# MCU.net
KiCad netlist of a schematic drawn in Altium Designer
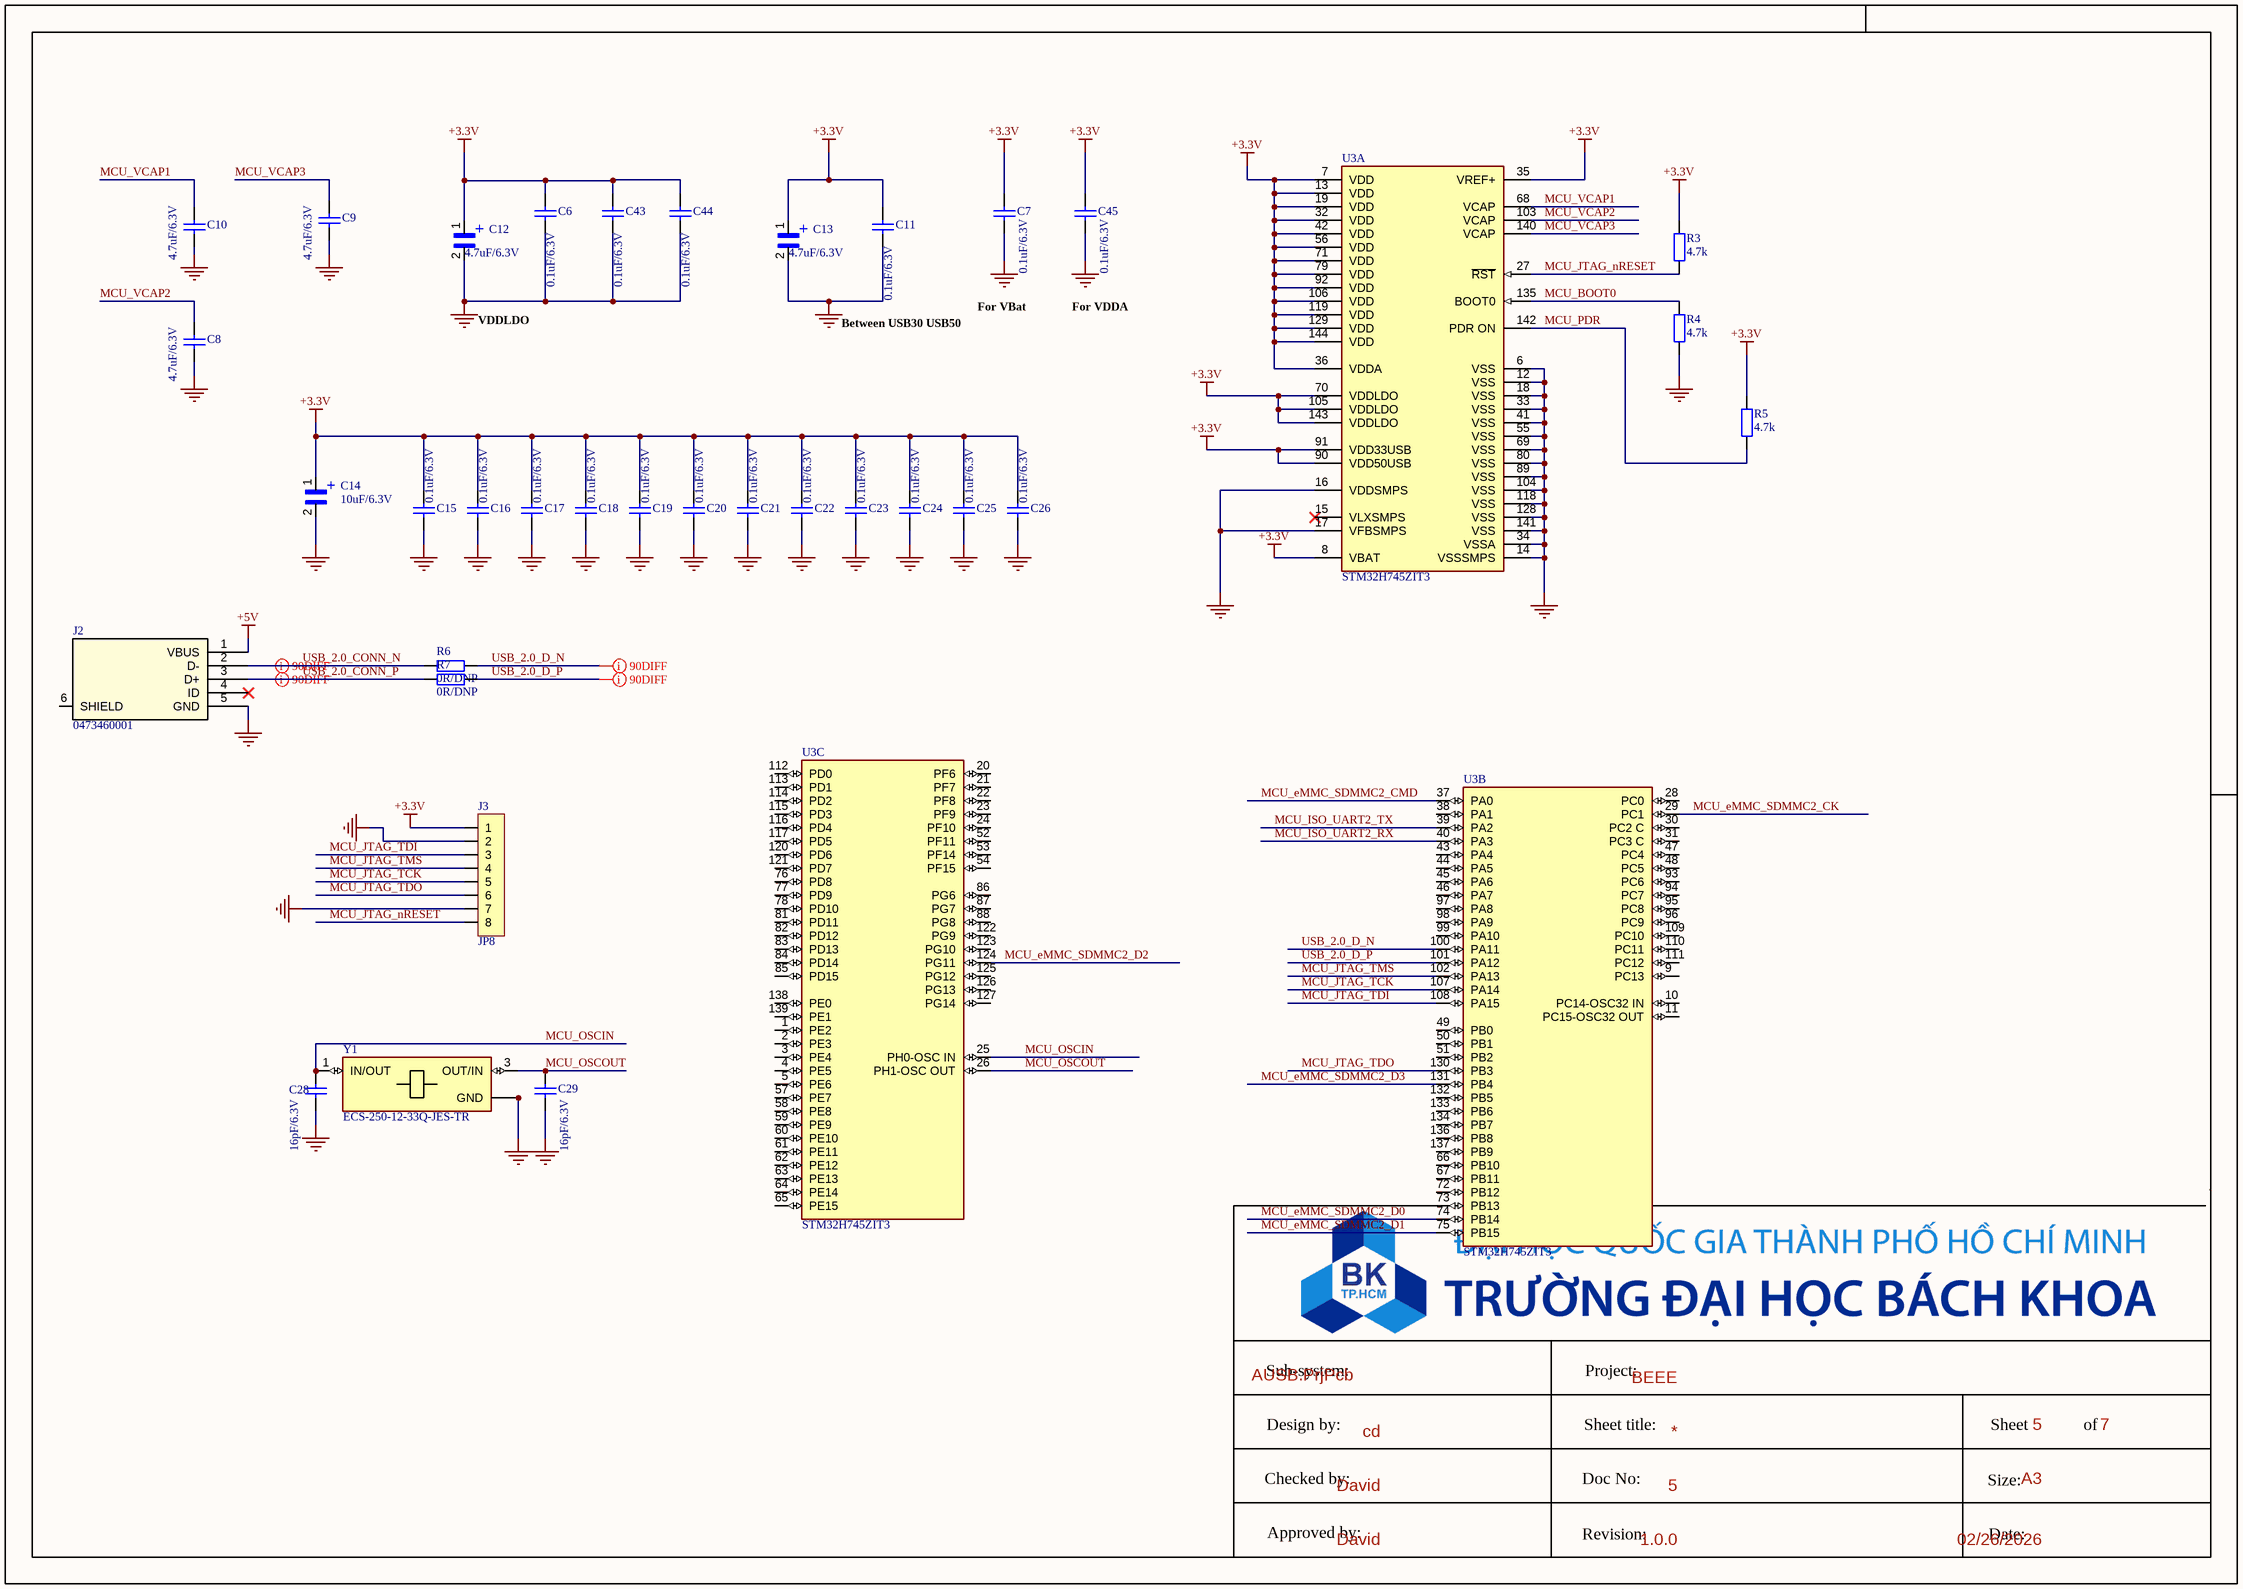
[diagram p0: MCU.SchDoc]

(export (version "E")
  (design (tool "Eeschema 10.0.6"))
  (components
    (comp (ref "C6")
      (value "0.1uF/6.3V")
      (footprint "CAP_C_1608X80")
      (description "4.7 µF ±20% 6.3V Ceramic Capacitor X7T 0402 (1005 Metric): GRT155D70J475ME13J")
      (libsource (lib "Altium_Lib_by_KhueNguyenCreator") (part "Tu 0402 33nF 10V"))
    )
    (comp (ref "C7")
      (value "0.1uF/6.3V")
      (footprint "CAP_C_1608X80")
      (description "CAPC")
      (libsource (lib "Altium_Lib_by_KhueNguyenCreator") (part "Tu 0402 33nF 10V"))
    )
    (comp (ref "C8")
      (value "4.7uF/6.3V")
      (footprint "CAP_C_1608X80")
      (description "4.7 µF ±20% 6.3V Ceramic Capacitor X7T 0402 (1005 Metric): GRT155D70J475ME13J")
      (libsource (lib "Altium_Lib_by_KhueNguyenCreator") (part "Tu 0402 33nF 10V"))
    )
    (comp (ref "C9")
      (value "4.7uF/6.3V")
      (footprint "CAP_C_1608X80")
      (description "4.7 µF ±20% 6.3V Ceramic Capacitor X7T 0402 (1005 Metric): GRT155D70J475ME13J")
      (libsource (lib "Altium_Lib_by_KhueNguyenCreator") (part "Tu 0402 33nF 10V"))
    )
    (comp (ref "C10")
      (value "4.7uF/6.3V")
      (footprint "CAP_C_1608X80")
      (description "4.7 µF ±20% 6.3V Ceramic Capacitor X7T 0402 (1005 Metric): GRT155D70J475ME13J")
      (libsource (lib "Altium_Lib_by_KhueNguyenCreator") (part "Tu 0402 33nF 10V"))
    )
    (comp (ref "C11")
      (value "0.1uF/6.3V")
      (footprint "CAP_C_1608X80")
      (description "CAPC")
      (libsource (lib "Altium_Lib_by_KhueNguyenCreator") (part "Tu 0402 33nF 10V"))
    )
    (comp (ref "C12")
      (value "4.7uF/6.3V")
      (footprint "CAP_MP_1608X90")
      (description "CAPP")
      (fields (field (name "MP") "TACL335M003RTA"))
      (libsource (lib "TACL335M003RTA") (part "TACL335M003RTA"))
    )
    (comp (ref "C13")
      (value "4.7uF/6.3V")
      (footprint "CAP_MP_1608X90")
      (description "CAPP")
      (fields (field (name "MP") "TACL335M003RTA"))
      (libsource (lib "TACL335M003RTA") (part "TACL335M003RTA"))
    )
    (comp (ref "C14")
      (value "10uF/6.3V")
      (footprint "CAP_MP_2012X170")
      (description "CAPP")
      (fields (field (name "MP") "TACR686M003RTA") (field (name "MF") "AVX"))
      (libsource (lib "TACR686M003RTA") (part "TACR686M003RTA"))
    )
    (comp (ref "C15")
      (value "0.1uF/6.3V")
      (footprint "CAP_C_1608X80")
      (description "CAPC")
      (libsource (lib "Altium_Lib_by_KhueNguyenCreator") (part "Tu 0402 33nF 10V"))
    )
    (comp (ref "C16")
      (value "0.1uF/6.3V")
      (footprint "CAP_C_1608X80")
      (description "CAPC")
      (libsource (lib "Altium_Lib_by_KhueNguyenCreator") (part "Tu 0402 33nF 10V"))
    )
    (comp (ref "C17")
      (value "0.1uF/6.3V")
      (footprint "CAP_C_1608X80")
      (description "CAPC")
      (libsource (lib "Altium_Lib_by_KhueNguyenCreator") (part "Tu 0402 33nF 10V"))
    )
    (comp (ref "C18")
      (value "0.1uF/6.3V")
      (footprint "CAP_C_1608X80")
      (description "CAPC")
      (libsource (lib "Altium_Lib_by_KhueNguyenCreator") (part "Tu 0402 33nF 10V"))
    )
    (comp (ref "C19")
      (value "0.1uF/6.3V")
      (footprint "CAP_C_1608X80")
      (description "CAPC")
      (libsource (lib "Altium_Lib_by_KhueNguyenCreator") (part "Tu 0402 33nF 10V"))
    )
    (comp (ref "C20")
      (value "0.1uF/6.3V")
      (footprint "CAP_C_1608X80")
      (description "CAPC")
      (libsource (lib "Altium_Lib_by_KhueNguyenCreator") (part "Tu 0402 33nF 10V"))
    )
    (comp (ref "C21")
      (value "0.1uF/6.3V")
      (footprint "CAP_C_1608X80")
      (description "CAPC")
      (libsource (lib "Altium_Lib_by_KhueNguyenCreator") (part "Tu 0402 33nF 10V"))
    )
    (comp (ref "C22")
      (value "0.1uF/6.3V")
      (footprint "CAP_C_1608X80")
      (description "CAPC")
      (libsource (lib "Altium_Lib_by_KhueNguyenCreator") (part "Tu 0402 33nF 10V"))
    )
    (comp (ref "C23")
      (value "0.1uF/6.3V")
      (footprint "CAP_C_1608X80")
      (description "CAPC")
      (libsource (lib "Altium_Lib_by_KhueNguyenCreator") (part "Tu 0402 33nF 10V"))
    )
    (comp (ref "C24")
      (value "0.1uF/6.3V")
      (footprint "CAP_C_1608X80")
      (description "CAPC")
      (libsource (lib "Altium_Lib_by_KhueNguyenCreator") (part "Tu 0402 33nF 10V"))
    )
    (comp (ref "C25")
      (value "0.1uF/6.3V")
      (footprint "CAP_C_1608X80")
      (description "CAPC")
      (libsource (lib "Altium_Lib_by_KhueNguyenCreator") (part "Tu 0402 33nF 10V"))
    )
    (comp (ref "C26")
      (value "0.1uF/6.3V")
      (footprint "CAP_C_1608X80")
      (description "CAPC")
      (libsource (lib "Altium_Lib_by_KhueNguyenCreator") (part "Tu 0402 33nF 10V"))
    )
    (comp (ref "C28")
      (value "16pF/6.3V")
      (footprint "CAP_C_1608X80")
      (description "CAPC")
      (libsource (lib "Altium_Lib_by_KhueNguyenCreator") (part "Tu 0402 33nF 10V"))
    )
    (comp (ref "C29")
      (value "16pF/6.3V")
      (footprint "CAP_C_1608X80")
      (description "CAPC")
      (libsource (lib "Altium_Lib_by_KhueNguyenCreator") (part "Tu 0402 33nF 10V"))
    )
    (comp (ref "C43")
      (value "0.1uF/6.3V")
      (footprint "CAP_C_1608X80")
      (description "4.7 µF ±20% 6.3V Ceramic Capacitor X7T 0402 (1005 Metric): GRT155D70J475ME13J")
      (libsource (lib "Altium_Lib_by_KhueNguyenCreator") (part "Tu 0402 33nF 10V"))
    )
    (comp (ref "C44")
      (value "0.1uF/6.3V")
      (footprint "CAP_C_1608X80")
      (description "4.7 µF ±20% 6.3V Ceramic Capacitor X7T 0402 (1005 Metric): GRT155D70J475ME13J")
      (libsource (lib "Altium_Lib_by_KhueNguyenCreator") (part "Tu 0402 33nF 10V"))
    )
    (comp (ref "C45")
      (value "0.1uF/6.3V")
      (footprint "CAP_C_1608X80")
      (description "CAPC")
      (libsource (lib "Altium_Lib_by_KhueNguyenCreator") (part "Tu 0402 33nF 10V"))
    )
    (comp (ref "J2")
      (value "0473460001")
      (footprint "47346-0001_MOL")
      (description "No Description Available")
      (libsource (lib "obc_ver2") (part "USB_micro"))
    )
    (comp (ref "J3") (value "JP8") (footprint "JP8-C1T") (libsource (lib "obc_ver2") (part "JP8")))
    (comp (ref "R3")
      (value "4.7k")
      (footprint "RES_C_1608X60")
      (description "RES")
      (libsource (lib "Altium_Lib_by_KhueNguyenCreator") (part "Tro 0603 1% 10k"))
    )
    (comp (ref "R4")
      (value "4.7k")
      (footprint "RES_C_1608X60")
      (description "RES")
      (libsource (lib "Altium_Lib_by_KhueNguyenCreator") (part "Tro 0603 1% 10k"))
    )
    (comp (ref "R5")
      (value "4.7k")
      (footprint "RES_C_1608X60")
      (description "RES")
      (libsource (lib "Altium_Lib_by_KhueNguyenCreator") (part "Tro 0603 1% 10k"))
    )
    (comp (ref "R6")
      (value "0R/DNP")
      (footprint "RES_C_1608X60")
      (description "RES SMD 12K OHM 1% 1/10W 0603, P/N: ERJ-3EKF1202V")
      (libsource (lib "Altium_Lib_by_KhueNguyenCreator") (part "Tro 0603 1% 1k"))
    )
    (comp (ref "R7")
      (value "0R/DNP")
      (footprint "RES_C_1608X60")
      (description "RES SMD 12K OHM 1% 1/10W 0603, P/N: ERJ-3EKF1202V")
      (libsource (lib "Altium_Lib_by_KhueNguyenCreator") (part "Tro 0603 1% 1k"))
    )
    (comp (ref "U3")
      (value "STM32H745ZIT3")
      (footprint "FP-LQFP144-1A-MFG")
      (description "HIGH-PERFORMANCE AND DSP WITH DP")
      (fields
        (field (name "MANUFACTURER PART NUMBER") "STM32H745ZIT6")
        (field (name "OCTOPART") "https://octopart.com/stm32h745zit6-stmicroelectronics-100293939")
      )
      (libsource (lib "AUSB") (part "CMP-12105-000054-1"))
    )
    (comp (ref "Y1")
      (value "ECS-250-12-33Q-JES-TR")
      (footprint "XTAL_ECS-250-12-33Q-JES-TR")
      (description "25 MHz Â±20ppm Crystal 12pF 40 Ohms 4-SMD, No Lead")
      (fields (field (name "MF") "ECS Inc."))
      (libsource (lib "ECS-250-12-33Q-JES-TR") (part "ECS-250-12-33Q-JES-TR"))
    )
  )
  (nets
    (net (code "1") (name "+3.3V") (class "Default")
      (node (ref "C11") (pin "1") (pinfunction "1_1") (pintype "passive"))
      (node (ref "C12") (pin "1") (pinfunction "1_1") (pintype "passive"))
      (node (ref "C13") (pin "1") (pinfunction "1_1") (pintype "passive"))
      (node (ref "C14") (pin "1") (pinfunction "1_1") (pintype "passive"))
      (node (ref "C15") (pin "1") (pinfunction "1_1") (pintype "passive"))
      (node (ref "C16") (pin "1") (pinfunction "1_1") (pintype "passive"))
      (node (ref "C17") (pin "1") (pinfunction "1_1") (pintype "passive"))
      (node (ref "C18") (pin "1") (pinfunction "1_1") (pintype "passive"))
      (node (ref "C19") (pin "1") (pinfunction "1_1") (pintype "passive"))
      (node (ref "C20") (pin "1") (pinfunction "1_1") (pintype "passive"))
      (node (ref "C21") (pin "1") (pinfunction "1_1") (pintype "passive"))
      (node (ref "C22") (pin "1") (pinfunction "1_1") (pintype "passive"))
      (node (ref "C23") (pin "1") (pinfunction "1_1") (pintype "passive"))
      (node (ref "C24") (pin "1") (pinfunction "1_1") (pintype "passive"))
      (node (ref "C25") (pin "1") (pinfunction "1_1") (pintype "passive"))
      (node (ref "C26") (pin "1") (pinfunction "1_1") (pintype "passive"))
      (node (ref "C43") (pin "1") (pinfunction "1_1") (pintype "passive"))
      (node (ref "C44") (pin "1") (pinfunction "1_1") (pintype "passive"))
      (node (ref "C45") (pin "1") (pinfunction "1_1") (pintype "passive"))
      (node (ref "C6") (pin "1") (pinfunction "1_1") (pintype "passive"))
      (node (ref "C7") (pin "1") (pinfunction "1_1") (pintype "passive"))
      (node (ref "J3") (pin "1") (pinfunction "1_1") (pintype "passive"))
      (node (ref "R3") (pin "1") (pinfunction "1_1") (pintype "passive"))
      (node (ref "R5") (pin "1") (pinfunction "1_1") (pintype "passive"))
      (node (ref "U3") (pin "105") (pinfunction "VDDLDO_105") (pintype "power_in"))
      (node (ref "U3") (pin "106") (pinfunction "VDD_106") (pintype "power_in"))
      (node (ref "U3") (pin "119") (pinfunction "VDD_119") (pintype "power_in"))
      (node (ref "U3") (pin "129") (pinfunction "VDD_129") (pintype "power_in"))
      (node (ref "U3") (pin "13") (pinfunction "VDD_13") (pintype "power_in"))
      (node (ref "U3") (pin "143") (pinfunction "VDDLDO_143") (pintype "power_in"))
      (node (ref "U3") (pin "144") (pinfunction "VDD_144") (pintype "power_in"))
      (node (ref "U3") (pin "19") (pinfunction "VDD_19") (pintype "power_in"))
      (node (ref "U3") (pin "32") (pinfunction "VDD_32") (pintype "power_in"))
      (node (ref "U3") (pin "35") (pinfunction "VREF+_35") (pintype "power_in"))
      (node (ref "U3") (pin "36") (pinfunction "VDDA_36") (pintype "power_in"))
      (node (ref "U3") (pin "42") (pinfunction "VDD_42") (pintype "power_in"))
      (node (ref "U3") (pin "56") (pinfunction "VDD_56") (pintype "power_in"))
      (node (ref "U3") (pin "7") (pinfunction "VDD_7") (pintype "power_in"))
      (node (ref "U3") (pin "70") (pinfunction "VDDLDO_70") (pintype "power_in"))
      (node (ref "U3") (pin "71") (pinfunction "VDD_71") (pintype "power_in"))
      (node (ref "U3") (pin "79") (pinfunction "VDD_79") (pintype "power_in"))
      (node (ref "U3") (pin "8") (pinfunction "VBAT_8") (pintype "power_in"))
      (node (ref "U3") (pin "90") (pinfunction "VDD50USB_90") (pintype "power_in"))
      (node (ref "U3") (pin "91") (pinfunction "VDD33USB_91") (pintype "power_in"))
      (node (ref "U3") (pin "92") (pinfunction "VDD_92") (pintype "power_in"))
    )
    (net (code "2") (name "+5V") (class "Default")
      (node (ref "J2") (pin "1") (pinfunction "VBUS_1") (pintype "passive"))
    )
    (net (code "3") (name "/MCU_BOOT0") (class "Default")
      (node (ref "R4") (pin "2") (pinfunction "2_2") (pintype "passive"))
      (node (ref "U3") (pin "135") (pinfunction "BOOT0_135") (pintype "input"))
    )
    (net (code "4") (name "/MCU_ISO_UART2_RX") (class "Default")
      (node (ref "U3") (pin "40") (pinfunction "PA3_40") (pintype "bidirectional"))
    )
    (net (code "5") (name "/MCU_ISO_UART2_TX") (class "Default")
      (node (ref "U3") (pin "39") (pinfunction "PA2_39") (pintype "bidirectional"))
    )
    (net (code "6") (name "/MCU_JTAG_TCK") (class "Default")
      (node (ref "J3") (pin "5") (pinfunction "5_5") (pintype "passive"))
      (node (ref "U3") (pin "107") (pinfunction "PA14_107") (pintype "bidirectional"))
    )
    (net (code "7") (name "/MCU_JTAG_TDI") (class "Default")
      (node (ref "J3") (pin "3") (pinfunction "3_3") (pintype "passive"))
      (node (ref "U3") (pin "108") (pinfunction "PA15_108") (pintype "bidirectional"))
    )
    (net (code "8") (name "/MCU_JTAG_TDO") (class "Default")
      (node (ref "J3") (pin "6") (pinfunction "6_6") (pintype "passive"))
      (node (ref "U3") (pin "130") (pinfunction "PB3_130") (pintype "bidirectional"))
    )
    (net (code "9") (name "/MCU_JTAG_TMS") (class "Default")
      (node (ref "J3") (pin "4") (pinfunction "4_4") (pintype "passive"))
      (node (ref "U3") (pin "102") (pinfunction "PA13_102") (pintype "bidirectional"))
    )
    (net (code "10") (name "/MCU_JTAG_nRESET") (class "Default")
      (node (ref "J3") (pin "8") (pinfunction "8_8") (pintype "passive"))
      (node (ref "R3") (pin "2") (pinfunction "2_2") (pintype "passive"))
      (node (ref "U3") (pin "27") (pinfunction "~{RST}_27") (pintype "input"))
    )
    (net (code "11") (name "/MCU_OSCIN") (class "Default")
      (node (ref "C28") (pin "2") (pinfunction "2_2") (pintype "passive"))
      (node (ref "U3") (pin "25") (pinfunction "PH0-OSC_IN_25") (pintype "bidirectional"))
      (node (ref "Y1") (pin "1") (pinfunction "IN/OUT_1") (pintype "bidirectional"))
    )
    (net (code "12") (name "/MCU_OSCOUT") (class "Default")
      (node (ref "C29") (pin "2") (pinfunction "2_2") (pintype "passive"))
      (node (ref "U3") (pin "26") (pinfunction "PH1-OSC_OUT_26") (pintype "bidirectional"))
      (node (ref "Y1") (pin "3") (pinfunction "OUT/IN_3") (pintype "bidirectional"))
    )
    (net (code "13") (name "/MCU_PDR") (class "Default")
      (node (ref "R5") (pin "2") (pinfunction "2_2") (pintype "passive"))
      (node (ref "U3") (pin "142") (pinfunction "PDR_ON_142") (pintype "passive"))
    )
    (net (code "14") (name "/MCU_VCAP1") (class "Default")
      (node (ref "C10") (pin "1") (pinfunction "1_1") (pintype "passive"))
      (node (ref "U3") (pin "68") (pinfunction "VCAP_68") (pintype "passive"))
    )
    (net (code "15") (name "/MCU_VCAP2") (class "Default")
      (node (ref "C8") (pin "1") (pinfunction "1_1") (pintype "passive"))
      (node (ref "U3") (pin "103") (pinfunction "VCAP_103") (pintype "passive"))
    )
    (net (code "16") (name "/MCU_VCAP3") (class "Default")
      (node (ref "C9") (pin "1") (pinfunction "1_1") (pintype "passive"))
      (node (ref "U3") (pin "140") (pinfunction "VCAP_140") (pintype "passive"))
    )
    (net (code "17") (name "/MCU_eMMC_SDMMC2_CK") (class "Default")
      (node (ref "U3") (pin "29") (pinfunction "PC1_29") (pintype "bidirectional"))
    )
    (net (code "18") (name "/MCU_eMMC_SDMMC2_CMD") (class "Default")
      (node (ref "U3") (pin "37") (pinfunction "PA0_37") (pintype "bidirectional"))
    )
    (net (code "19") (name "/MCU_eMMC_SDMMC2_D0") (class "Default")
      (node (ref "U3") (pin "74") (pinfunction "PB14_74") (pintype "bidirectional"))
    )
    (net (code "20") (name "/MCU_eMMC_SDMMC2_D1") (class "Default")
      (node (ref "U3") (pin "75") (pinfunction "PB15_75") (pintype "bidirectional"))
    )
    (net (code "21") (name "/MCU_eMMC_SDMMC2_D2") (class "Default")
      (node (ref "U3") (pin "124") (pinfunction "PG11_124") (pintype "bidirectional"))
    )
    (net (code "22") (name "/MCU_eMMC_SDMMC2_D3") (class "Default")
      (node (ref "U3") (pin "131") (pinfunction "PB4_131") (pintype "bidirectional"))
    )
    (net (code "23") (name "/USB_2.0_CONN_N") (class "Default")
      (node (ref "J2") (pin "2") (pinfunction "D-_2") (pintype "passive"))
      (node (ref "R6") (pin "1") (pinfunction "1_1") (pintype "passive"))
    )
    (net (code "24") (name "/USB_2.0_CONN_P") (class "Default")
      (node (ref "J2") (pin "3") (pinfunction "D+_3") (pintype "passive"))
      (node (ref "R7") (pin "1") (pinfunction "1_1") (pintype "passive"))
    )
    (net (code "25") (name "/USB_2.0_D_N") (class "Default")
      (node (ref "R6") (pin "2") (pinfunction "2_2") (pintype "passive"))
      (node (ref "U3") (pin "100") (pinfunction "PA11_100") (pintype "bidirectional"))
    )
    (net (code "26") (name "/USB_2.0_D_P") (class "Default")
      (node (ref "R7") (pin "2") (pinfunction "2_2") (pintype "passive"))
      (node (ref "U3") (pin "101") (pinfunction "PA12_101") (pintype "bidirectional"))
    )
    (net (code "27") (name "GND") (class "Default")
      (node (ref "C10") (pin "2") (pinfunction "2_2") (pintype "passive"))
      (node (ref "C11") (pin "2") (pinfunction "2_2") (pintype "passive"))
      (node (ref "C12") (pin "2") (pinfunction "2_2") (pintype "passive"))
      (node (ref "C13") (pin "2") (pinfunction "2_2") (pintype "passive"))
      (node (ref "C14") (pin "2") (pinfunction "2_2") (pintype "passive"))
      (node (ref "C15") (pin "2") (pinfunction "2_2") (pintype "passive"))
      (node (ref "C16") (pin "2") (pinfunction "2_2") (pintype "passive"))
      (node (ref "C17") (pin "2") (pinfunction "2_2") (pintype "passive"))
      (node (ref "C18") (pin "2") (pinfunction "2_2") (pintype "passive"))
      (node (ref "C19") (pin "2") (pinfunction "2_2") (pintype "passive"))
      (node (ref "C20") (pin "2") (pinfunction "2_2") (pintype "passive"))
      (node (ref "C21") (pin "2") (pinfunction "2_2") (pintype "passive"))
      (node (ref "C22") (pin "2") (pinfunction "2_2") (pintype "passive"))
      (node (ref "C23") (pin "2") (pinfunction "2_2") (pintype "passive"))
      (node (ref "C24") (pin "2") (pinfunction "2_2") (pintype "passive"))
      (node (ref "C25") (pin "2") (pinfunction "2_2") (pintype "passive"))
      (node (ref "C26") (pin "2") (pinfunction "2_2") (pintype "passive"))
      (node (ref "C28") (pin "1") (pinfunction "1_1") (pintype "passive"))
      (node (ref "C29") (pin "1") (pinfunction "1_1") (pintype "passive"))
      (node (ref "C43") (pin "2") (pinfunction "2_2") (pintype "passive"))
      (node (ref "C44") (pin "2") (pinfunction "2_2") (pintype "passive"))
      (node (ref "C45") (pin "2") (pinfunction "2_2") (pintype "passive"))
      (node (ref "C6") (pin "2") (pinfunction "2_2") (pintype "passive"))
      (node (ref "C7") (pin "2") (pinfunction "2_2") (pintype "passive"))
      (node (ref "C8") (pin "2") (pinfunction "2_2") (pintype "passive"))
      (node (ref "C9") (pin "2") (pinfunction "2_2") (pintype "passive"))
      (node (ref "J2") (pin "5") (pinfunction "GND_5") (pintype "power_in"))
      (node (ref "J3") (pin "2") (pinfunction "2_2") (pintype "passive"))
      (node (ref "J3") (pin "7") (pinfunction "7_7") (pintype "passive"))
      (node (ref "R4") (pin "1") (pinfunction "1_1") (pintype "passive"))
      (node (ref "U3") (pin "104") (pinfunction "VSS_104") (pintype "power_in"))
      (node (ref "U3") (pin "118") (pinfunction "VSS_118") (pintype "power_in"))
      (node (ref "U3") (pin "12") (pinfunction "VSS_12") (pintype "power_in"))
      (node (ref "U3") (pin "128") (pinfunction "VSS_128") (pintype "power_in"))
      (node (ref "U3") (pin "14") (pinfunction "VSSSMPS_14") (pintype "power_in"))
      (node (ref "U3") (pin "141") (pinfunction "VSS_141") (pintype "power_in"))
      (node (ref "U3") (pin "16") (pinfunction "VDDSMPS_16") (pintype "power_in"))
      (node (ref "U3") (pin "17") (pinfunction "VFBSMPS_17") (pintype "power_in"))
      (node (ref "U3") (pin "18") (pinfunction "VSS_18") (pintype "power_in"))
      (node (ref "U3") (pin "33") (pinfunction "VSS_33") (pintype "power_in"))
      (node (ref "U3") (pin "34") (pinfunction "VSSA_34") (pintype "power_in"))
      (node (ref "U3") (pin "41") (pinfunction "VSS_41") (pintype "power_in"))
      (node (ref "U3") (pin "55") (pinfunction "VSS_55") (pintype "power_in"))
      (node (ref "U3") (pin "6") (pinfunction "VSS_6") (pintype "power_in"))
      (node (ref "U3") (pin "69") (pinfunction "VSS_69") (pintype "power_in"))
      (node (ref "U3") (pin "80") (pinfunction "VSS_80") (pintype "power_in"))
      (node (ref "U3") (pin "89") (pinfunction "VSS_89") (pintype "power_in"))
      (node (ref "Y1") (pin "2") (pinfunction "GND_2") (pintype "power_in"))
      (node (ref "Y1") (pin "4") (pinfunction "GND_4") (pintype "power_in"))
    )
    (net (code "28") (name "unconnected-(J2-ID-Pad4)") (class "Default")
      (node (ref "J2") (pin "4") (pinfunction "ID_4") (pintype "passive+no_connect"))
    )
    (net (code "29") (name "unconnected-(J2-SHIELD-Pad6)") (class "Default")
      (node (ref "J2") (pin "6") (pinfunction "SHIELD_6") (pintype "passive"))
    )
    (net (code "30") (name "unconnected-(U3A-VLXSMPS-Pad15)") (class "Default")
      (node (ref "U3") (pin "15") (pinfunction "VLXSMPS_15") (pintype "power_in+no_connect"))
    )
    (net (code "31") (name "unconnected-(U3B-PA1-Pad38)") (class "Default")
      (node (ref "U3") (pin "38") (pinfunction "PA1_38") (pintype "bidirectional"))
    )
    (net (code "32") (name "unconnected-(U3B-PA4-Pad43)") (class "Default")
      (node (ref "U3") (pin "43") (pinfunction "PA4_43") (pintype "bidirectional"))
    )
    (net (code "33") (name "unconnected-(U3B-PA5-Pad44)") (class "Default")
      (node (ref "U3") (pin "44") (pinfunction "PA5_44") (pintype "bidirectional"))
    )
    (net (code "34") (name "unconnected-(U3B-PA6-Pad45)") (class "Default")
      (node (ref "U3") (pin "45") (pinfunction "PA6_45") (pintype "bidirectional"))
    )
    (net (code "35") (name "unconnected-(U3B-PA7-Pad46)") (class "Default")
      (node (ref "U3") (pin "46") (pinfunction "PA7_46") (pintype "bidirectional"))
    )
    (net (code "36") (name "unconnected-(U3B-PA8-Pad97)") (class "Default")
      (node (ref "U3") (pin "97") (pinfunction "PA8_97") (pintype "bidirectional"))
    )
    (net (code "37") (name "unconnected-(U3B-PA9-Pad98)") (class "Default")
      (node (ref "U3") (pin "98") (pinfunction "PA9_98") (pintype "bidirectional"))
    )
    (net (code "38") (name "unconnected-(U3B-PA10-Pad99)") (class "Default")
      (node (ref "U3") (pin "99") (pinfunction "PA10_99") (pintype "bidirectional"))
    )
    (net (code "39") (name "unconnected-(U3B-PB0-Pad49)") (class "Default")
      (node (ref "U3") (pin "49") (pinfunction "PB0_49") (pintype "bidirectional"))
    )
    (net (code "40") (name "unconnected-(U3B-PB1-Pad50)") (class "Default")
      (node (ref "U3") (pin "50") (pinfunction "PB1_50") (pintype "bidirectional"))
    )
    (net (code "41") (name "unconnected-(U3B-PB2-Pad51)") (class "Default")
      (node (ref "U3") (pin "51") (pinfunction "PB2_51") (pintype "bidirectional"))
    )
    (net (code "42") (name "unconnected-(U3B-PB5-Pad132)") (class "Default")
      (node (ref "U3") (pin "132") (pinfunction "PB5_132") (pintype "bidirectional"))
    )
    (net (code "43") (name "unconnected-(U3B-PB6-Pad133)") (class "Default")
      (node (ref "U3") (pin "133") (pinfunction "PB6_133") (pintype "bidirectional"))
    )
    (net (code "44") (name "unconnected-(U3B-PB7-Pad134)") (class "Default")
      (node (ref "U3") (pin "134") (pinfunction "PB7_134") (pintype "bidirectional"))
    )
    (net (code "45") (name "unconnected-(U3B-PB8-Pad136)") (class "Default")
      (node (ref "U3") (pin "136") (pinfunction "PB8_136") (pintype "bidirectional"))
    )
    (net (code "46") (name "unconnected-(U3B-PB9-Pad137)") (class "Default")
      (node (ref "U3") (pin "137") (pinfunction "PB9_137") (pintype "bidirectional"))
    )
    (net (code "47") (name "unconnected-(U3B-PB10-Pad66)") (class "Default")
      (node (ref "U3") (pin "66") (pinfunction "PB10_66") (pintype "bidirectional"))
    )
    (net (code "48") (name "unconnected-(U3B-PB11-Pad67)") (class "Default")
      (node (ref "U3") (pin "67") (pinfunction "PB11_67") (pintype "bidirectional"))
    )
    (net (code "49") (name "unconnected-(U3B-PB12-Pad72)") (class "Default")
      (node (ref "U3") (pin "72") (pinfunction "PB12_72") (pintype "bidirectional"))
    )
    (net (code "50") (name "unconnected-(U3B-PB13-Pad73)") (class "Default")
      (node (ref "U3") (pin "73") (pinfunction "PB13_73") (pintype "bidirectional"))
    )
    (net (code "51") (name "unconnected-(U3B-PC0-Pad28)") (class "Default")
      (node (ref "U3") (pin "28") (pinfunction "PC0_28") (pintype "bidirectional"))
    )
    (net (code "52") (name "unconnected-(U3B-PC2_C-Pad30)") (class "Default")
      (node (ref "U3") (pin "30") (pinfunction "PC2_C_30") (pintype "bidirectional"))
    )
    (net (code "53") (name "unconnected-(U3B-PC3_C-Pad31)") (class "Default")
      (node (ref "U3") (pin "31") (pinfunction "PC3_C_31") (pintype "bidirectional"))
    )
    (net (code "54") (name "unconnected-(U3B-PC4-Pad47)") (class "Default")
      (node (ref "U3") (pin "47") (pinfunction "PC4_47") (pintype "bidirectional"))
    )
    (net (code "55") (name "unconnected-(U3B-PC5-Pad48)") (class "Default")
      (node (ref "U3") (pin "48") (pinfunction "PC5_48") (pintype "bidirectional"))
    )
    (net (code "56") (name "unconnected-(U3B-PC6-Pad93)") (class "Default")
      (node (ref "U3") (pin "93") (pinfunction "PC6_93") (pintype "bidirectional"))
    )
    (net (code "57") (name "unconnected-(U3B-PC7-Pad94)") (class "Default")
      (node (ref "U3") (pin "94") (pinfunction "PC7_94") (pintype "bidirectional"))
    )
    (net (code "58") (name "unconnected-(U3B-PC8-Pad95)") (class "Default")
      (node (ref "U3") (pin "95") (pinfunction "PC8_95") (pintype "bidirectional"))
    )
    (net (code "59") (name "unconnected-(U3B-PC9-Pad96)") (class "Default")
      (node (ref "U3") (pin "96") (pinfunction "PC9_96") (pintype "bidirectional"))
    )
    (net (code "60") (name "unconnected-(U3B-PC10-Pad109)") (class "Default")
      (node (ref "U3") (pin "109") (pinfunction "PC10_109") (pintype "bidirectional"))
    )
    (net (code "61") (name "unconnected-(U3B-PC11-Pad110)") (class "Default")
      (node (ref "U3") (pin "110") (pinfunction "PC11_110") (pintype "bidirectional"))
    )
    (net (code "62") (name "unconnected-(U3B-PC12-Pad111)") (class "Default")
      (node (ref "U3") (pin "111") (pinfunction "PC12_111") (pintype "bidirectional"))
    )
    (net (code "63") (name "unconnected-(U3B-PC13-Pad9)") (class "Default")
      (node (ref "U3") (pin "9") (pinfunction "PC13_9") (pintype "bidirectional"))
    )
    (net (code "64") (name "unconnected-(U3B-PC14-OSC32_IN-Pad10)") (class "Default")
      (node (ref "U3") (pin "10") (pinfunction "PC14-OSC32_IN_10") (pintype "bidirectional"))
    )
    (net (code "65") (name "unconnected-(U3B-PC15-OSC32_OUT-Pad11)") (class "Default")
      (node (ref "U3") (pin "11") (pinfunction "PC15-OSC32_OUT_11") (pintype "bidirectional"))
    )
    (net (code "66") (name "unconnected-(U3C-PD0-Pad112)") (class "Default")
      (node (ref "U3") (pin "112") (pinfunction "PD0_112") (pintype "bidirectional"))
    )
    (net (code "67") (name "unconnected-(U3C-PD1-Pad113)") (class "Default")
      (node (ref "U3") (pin "113") (pinfunction "PD1_113") (pintype "bidirectional"))
    )
    (net (code "68") (name "unconnected-(U3C-PD2-Pad114)") (class "Default")
      (node (ref "U3") (pin "114") (pinfunction "PD2_114") (pintype "bidirectional"))
    )
    (net (code "69") (name "unconnected-(U3C-PD3-Pad115)") (class "Default")
      (node (ref "U3") (pin "115") (pinfunction "PD3_115") (pintype "bidirectional"))
    )
    (net (code "70") (name "unconnected-(U3C-PD4-Pad116)") (class "Default")
      (node (ref "U3") (pin "116") (pinfunction "PD4_116") (pintype "bidirectional"))
    )
    (net (code "71") (name "unconnected-(U3C-PD5-Pad117)") (class "Default")
      (node (ref "U3") (pin "117") (pinfunction "PD5_117") (pintype "bidirectional"))
    )
    (net (code "72") (name "unconnected-(U3C-PD6-Pad120)") (class "Default")
      (node (ref "U3") (pin "120") (pinfunction "PD6_120") (pintype "bidirectional"))
    )
    (net (code "73") (name "unconnected-(U3C-PD7-Pad121)") (class "Default")
      (node (ref "U3") (pin "121") (pinfunction "PD7_121") (pintype "bidirectional"))
    )
    (net (code "74") (name "unconnected-(U3C-PD8-Pad76)") (class "Default")
      (node (ref "U3") (pin "76") (pinfunction "PD8_76") (pintype "bidirectional"))
    )
    (net (code "75") (name "unconnected-(U3C-PD9-Pad77)") (class "Default")
      (node (ref "U3") (pin "77") (pinfunction "PD9_77") (pintype "bidirectional"))
    )
    (net (code "76") (name "unconnected-(U3C-PD10-Pad78)") (class "Default")
      (node (ref "U3") (pin "78") (pinfunction "PD10_78") (pintype "bidirectional"))
    )
    (net (code "77") (name "unconnected-(U3C-PD11-Pad81)") (class "Default")
      (node (ref "U3") (pin "81") (pinfunction "PD11_81") (pintype "bidirectional"))
    )
    (net (code "78") (name "unconnected-(U3C-PD12-Pad82)") (class "Default")
      (node (ref "U3") (pin "82") (pinfunction "PD12_82") (pintype "bidirectional"))
    )
    (net (code "79") (name "unconnected-(U3C-PD13-Pad83)") (class "Default")
      (node (ref "U3") (pin "83") (pinfunction "PD13_83") (pintype "bidirectional"))
    )
    (net (code "80") (name "unconnected-(U3C-PD14-Pad84)") (class "Default")
      (node (ref "U3") (pin "84") (pinfunction "PD14_84") (pintype "bidirectional"))
    )
    (net (code "81") (name "unconnected-(U3C-PD15-Pad85)") (class "Default")
      (node (ref "U3") (pin "85") (pinfunction "PD15_85") (pintype "bidirectional"))
    )
    (net (code "82") (name "unconnected-(U3C-PE0-Pad138)") (class "Default")
      (node (ref "U3") (pin "138") (pinfunction "PE0_138") (pintype "bidirectional"))
    )
    (net (code "83") (name "unconnected-(U3C-PE1-Pad139)") (class "Default")
      (node (ref "U3") (pin "139") (pinfunction "PE1_139") (pintype "bidirectional"))
    )
    (net (code "84") (name "unconnected-(U3C-PE2-Pad1)") (class "Default")
      (node (ref "U3") (pin "1") (pinfunction "PE2_1") (pintype "bidirectional"))
    )
    (net (code "85") (name "unconnected-(U3C-PE3-Pad2)") (class "Default")
      (node (ref "U3") (pin "2") (pinfunction "PE3_2") (pintype "bidirectional"))
    )
    (net (code "86") (name "unconnected-(U3C-PE4-Pad3)") (class "Default")
      (node (ref "U3") (pin "3") (pinfunction "PE4_3") (pintype "bidirectional"))
    )
    (net (code "87") (name "unconnected-(U3C-PE5-Pad4)") (class "Default")
      (node (ref "U3") (pin "4") (pinfunction "PE5_4") (pintype "bidirectional"))
    )
    (net (code "88") (name "unconnected-(U3C-PE6-Pad5)") (class "Default")
      (node (ref "U3") (pin "5") (pinfunction "PE6_5") (pintype "bidirectional"))
    )
    (net (code "89") (name "unconnected-(U3C-PE7-Pad57)") (class "Default")
      (node (ref "U3") (pin "57") (pinfunction "PE7_57") (pintype "bidirectional"))
    )
    (net (code "90") (name "unconnected-(U3C-PE8-Pad58)") (class "Default")
      (node (ref "U3") (pin "58") (pinfunction "PE8_58") (pintype "bidirectional"))
    )
    (net (code "91") (name "unconnected-(U3C-PE9-Pad59)") (class "Default")
      (node (ref "U3") (pin "59") (pinfunction "PE9_59") (pintype "bidirectional"))
    )
    (net (code "92") (name "unconnected-(U3C-PE10-Pad60)") (class "Default")
      (node (ref "U3") (pin "60") (pinfunction "PE10_60") (pintype "bidirectional"))
    )
    (net (code "93") (name "unconnected-(U3C-PE11-Pad61)") (class "Default")
      (node (ref "U3") (pin "61") (pinfunction "PE11_61") (pintype "bidirectional"))
    )
    (net (code "94") (name "unconnected-(U3C-PE12-Pad62)") (class "Default")
      (node (ref "U3") (pin "62") (pinfunction "PE12_62") (pintype "bidirectional"))
    )
    (net (code "95") (name "unconnected-(U3C-PE13-Pad63)") (class "Default")
      (node (ref "U3") (pin "63") (pinfunction "PE13_63") (pintype "bidirectional"))
    )
    (net (code "96") (name "unconnected-(U3C-PE14-Pad64)") (class "Default")
      (node (ref "U3") (pin "64") (pinfunction "PE14_64") (pintype "bidirectional"))
    )
    (net (code "97") (name "unconnected-(U3C-PE15-Pad65)") (class "Default")
      (node (ref "U3") (pin "65") (pinfunction "PE15_65") (pintype "bidirectional"))
    )
    (net (code "98") (name "unconnected-(U3C-PF6-Pad20)") (class "Default")
      (node (ref "U3") (pin "20") (pinfunction "PF6_20") (pintype "bidirectional"))
    )
    (net (code "99") (name "unconnected-(U3C-PF7-Pad21)") (class "Default")
      (node (ref "U3") (pin "21") (pinfunction "PF7_21") (pintype "bidirectional"))
    )
    (net (code "100") (name "unconnected-(U3C-PF8-Pad22)") (class "Default")
      (node (ref "U3") (pin "22") (pinfunction "PF8_22") (pintype "bidirectional"))
    )
    (net (code "101") (name "unconnected-(U3C-PF9-Pad23)") (class "Default")
      (node (ref "U3") (pin "23") (pinfunction "PF9_23") (pintype "bidirectional"))
    )
    (net (code "102") (name "unconnected-(U3C-PF10-Pad24)") (class "Default")
      (node (ref "U3") (pin "24") (pinfunction "PF10_24") (pintype "bidirectional"))
    )
    (net (code "103") (name "unconnected-(U3C-PF11-Pad52)") (class "Default")
      (node (ref "U3") (pin "52") (pinfunction "PF11_52") (pintype "bidirectional"))
    )
    (net (code "104") (name "unconnected-(U3C-PF14-Pad53)") (class "Default")
      (node (ref "U3") (pin "53") (pinfunction "PF14_53") (pintype "bidirectional"))
    )
    (net (code "105") (name "unconnected-(U3C-PF15-Pad54)") (class "Default")
      (node (ref "U3") (pin "54") (pinfunction "PF15_54") (pintype "bidirectional"))
    )
    (net (code "106") (name "unconnected-(U3C-PG6-Pad86)") (class "Default")
      (node (ref "U3") (pin "86") (pinfunction "PG6_86") (pintype "bidirectional"))
    )
    (net (code "107") (name "unconnected-(U3C-PG7-Pad87)") (class "Default")
      (node (ref "U3") (pin "87") (pinfunction "PG7_87") (pintype "bidirectional"))
    )
    (net (code "108") (name "unconnected-(U3C-PG8-Pad88)") (class "Default")
      (node (ref "U3") (pin "88") (pinfunction "PG8_88") (pintype "bidirectional"))
    )
    (net (code "109") (name "unconnected-(U3C-PG9-Pad122)") (class "Default")
      (node (ref "U3") (pin "122") (pinfunction "PG9_122") (pintype "bidirectional"))
    )
    (net (code "110") (name "unconnected-(U3C-PG10-Pad123)") (class "Default")
      (node (ref "U3") (pin "123") (pinfunction "PG10_123") (pintype "bidirectional"))
    )
    (net (code "111") (name "unconnected-(U3C-PG12-Pad125)") (class "Default")
      (node (ref "U3") (pin "125") (pinfunction "PG12_125") (pintype "bidirectional"))
    )
    (net (code "112") (name "unconnected-(U3C-PG13-Pad126)") (class "Default")
      (node (ref "U3") (pin "126") (pinfunction "PG13_126") (pintype "bidirectional"))
    )
    (net (code "113") (name "unconnected-(U3C-PG14-Pad127)") (class "Default")
      (node (ref "U3") (pin "127") (pinfunction "PG14_127") (pintype "bidirectional"))
    )
  )
)
